# Bias_Current_Source.net
KiCad netlist of a schematic drawn in Altium Designer
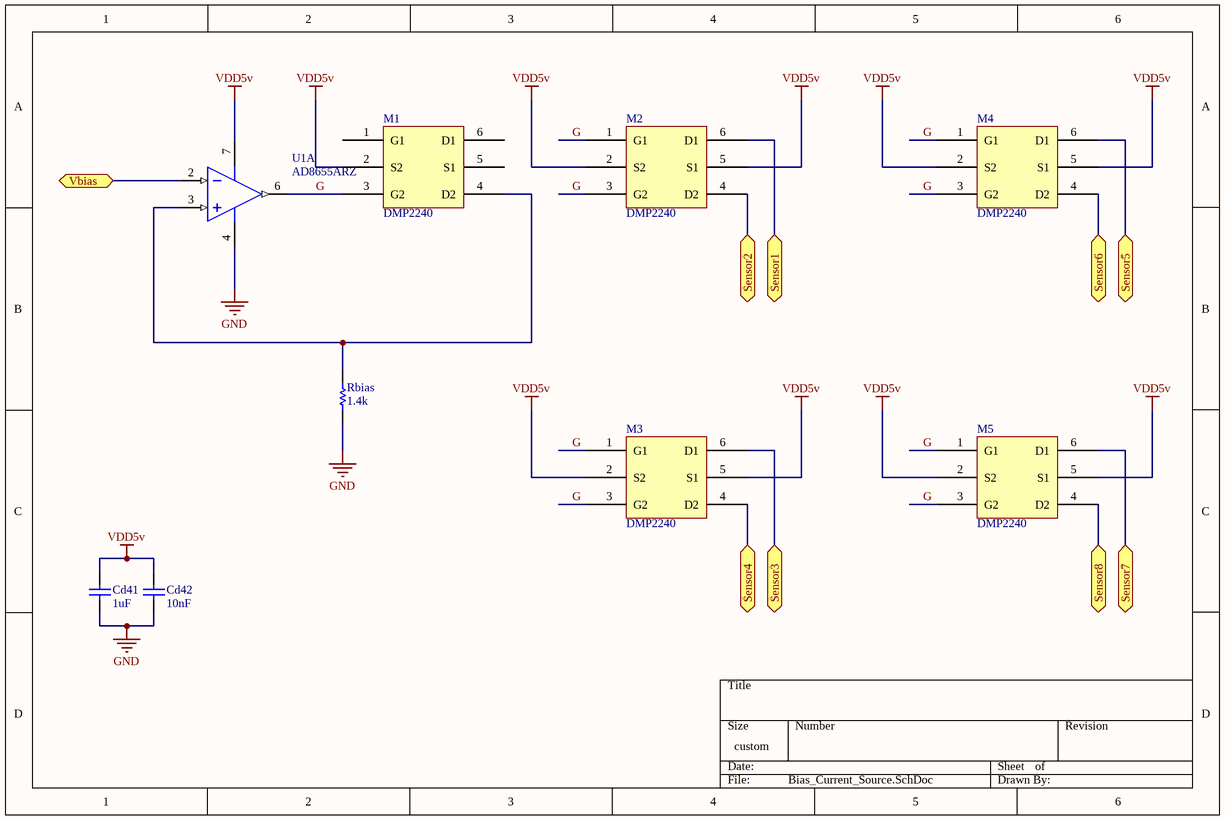
[diagram p0: Bias_Current_Source.SchDoc]

(export (version "E")
  (design (tool "Eeschema 10.0.6"))
  (components
    (comp (ref "Cd41")
      (value "1uF")
      (footprint "1608[0603]")
      (description "Capacitor")
      (fields (field (name "Comment") "Cap") (field (name "PUBLISHER") "Altium Limited"))
      (libsource (lib "Miscellaneous Devices") (part "Cap"))
    )
    (comp (ref "Cd42")
      (value "10nF")
      (footprint "1608[0603]")
      (description "Capacitor")
      (fields (field (name "Comment") "Cap") (field (name "PUBLISHER") "Altium Limited"))
      (libsource (lib "Miscellaneous Devices") (part "Cap"))
    )
    (comp (ref "M1") (value "DMP2240") (footprint "SO-G6/E2.4") (libsource (lib "custom") (part "DMP2240")))
    (comp (ref "M2") (value "DMP2240") (footprint "SO-G6/E2.4") (libsource (lib "custom") (part "DMP2240")))
    (comp (ref "M3") (value "DMP2240") (footprint "SO-G6/E2.4") (libsource (lib "custom") (part "DMP2240")))
    (comp (ref "M4") (value "DMP2240") (footprint "SO-G6/E2.4") (libsource (lib "custom") (part "DMP2240")))
    (comp (ref "M5") (value "DMP2240") (footprint "SO-G6/E2.4") (libsource (lib "custom") (part "DMP2240")))
    (comp (ref "Rbias")
      (value "1.4k")
      (footprint "1608[0603]")
      (description "Resistor")
      (fields (field (name "Comment") "Res1") (field (name "PUBLISHER") "Altium Limited"))
      (libsource (lib "Miscellaneous Devices") (part "Res1"))
    )
    (comp (ref "U1")
      (value "AD8655ARZ")
      (footprint "ADI-R-8_N")
      (fields (field (name "GENERIC PART NUMBER") "AD8655") (field (name "MANUFACTURER") "Analog Devices"))
      (libsource (lib "Analog Devices Operational Amplifiers") (part "AD8655ARZ"))
    )
  )
  (nets
    (net (code "1") (name "/G") (class "Default")
      (node (ref "M1") (pin "3") (pinfunction "G2_3") (pintype "passive"))
      (node (ref "M2") (pin "1") (pinfunction "G1_1") (pintype "passive"))
      (node (ref "M2") (pin "3") (pinfunction "G2_3") (pintype "passive"))
      (node (ref "M3") (pin "1") (pinfunction "G1_1") (pintype "passive"))
      (node (ref "M3") (pin "3") (pinfunction "G2_3") (pintype "passive"))
      (node (ref "M4") (pin "1") (pinfunction "G1_1") (pintype "passive"))
      (node (ref "M4") (pin "3") (pinfunction "G2_3") (pintype "passive"))
      (node (ref "M5") (pin "1") (pinfunction "G1_1") (pintype "passive"))
      (node (ref "M5") (pin "3") (pinfunction "G2_3") (pintype "passive"))
      (node (ref "U1") (pin "6") (pinfunction "OUT_6") (pintype "output"))
    )
    (net (code "2") (name "/Sensor1") (class "Default")
      (node (ref "M2") (pin "6") (pinfunction "D1_6") (pintype "passive"))
    )
    (net (code "3") (name "/Sensor2") (class "Default")
      (node (ref "M2") (pin "4") (pinfunction "D2_4") (pintype "passive"))
    )
    (net (code "4") (name "/Sensor3") (class "Default")
      (node (ref "M3") (pin "6") (pinfunction "D1_6") (pintype "passive"))
    )
    (net (code "5") (name "/Sensor4") (class "Default")
      (node (ref "M3") (pin "4") (pinfunction "D2_4") (pintype "passive"))
    )
    (net (code "6") (name "/Sensor5") (class "Default")
      (node (ref "M4") (pin "6") (pinfunction "D1_6") (pintype "passive"))
    )
    (net (code "7") (name "/Sensor6") (class "Default")
      (node (ref "M4") (pin "4") (pinfunction "D2_4") (pintype "passive"))
    )
    (net (code "8") (name "/Sensor7") (class "Default")
      (node (ref "M5") (pin "6") (pinfunction "D1_6") (pintype "passive"))
    )
    (net (code "9") (name "/Sensor8") (class "Default")
      (node (ref "M5") (pin "4") (pinfunction "D2_4") (pintype "passive"))
    )
    (net (code "10") (name "/Vbias") (class "Default")
      (node (ref "U1") (pin "2") (pinfunction "-IN_2") (pintype "input"))
    )
    (net (code "11") (name "GND") (class "Default")
      (node (ref "Cd41") (pin "2") (pinfunction "2_2") (pintype "passive"))
      (node (ref "Cd42") (pin "2") (pinfunction "2_2") (pintype "passive"))
      (node (ref "Rbias") (pin "2") (pinfunction "2_2") (pintype "passive"))
      (node (ref "U1") (pin "4") (pinfunction "-V_4") (pintype "power_in"))
    )
    (net (code "12") (name "Net-(M1-D2)") (class "Default")
      (node (ref "M1") (pin "4") (pinfunction "D2_4") (pintype "passive"))
      (node (ref "Rbias") (pin "1") (pinfunction "1_1") (pintype "passive"))
      (node (ref "U1") (pin "3") (pinfunction "+IN_3") (pintype "input"))
    )
    (net (code "13") (name "VDD5v") (class "Default")
      (node (ref "Cd41") (pin "1") (pinfunction "1_1") (pintype "passive"))
      (node (ref "Cd42") (pin "1") (pinfunction "1_1") (pintype "passive"))
      (node (ref "M1") (pin "2") (pinfunction "S2_2") (pintype "passive"))
      (node (ref "M2") (pin "2") (pinfunction "S2_2") (pintype "passive"))
      (node (ref "M2") (pin "5") (pinfunction "S1_5") (pintype "passive"))
      (node (ref "M3") (pin "2") (pinfunction "S2_2") (pintype "passive"))
      (node (ref "M3") (pin "5") (pinfunction "S1_5") (pintype "passive"))
      (node (ref "M4") (pin "2") (pinfunction "S2_2") (pintype "passive"))
      (node (ref "M4") (pin "5") (pinfunction "S1_5") (pintype "passive"))
      (node (ref "M5") (pin "2") (pinfunction "S2_2") (pintype "passive"))
      (node (ref "M5") (pin "5") (pinfunction "S1_5") (pintype "passive"))
      (node (ref "U1") (pin "7") (pinfunction "+V_7") (pintype "power_in"))
    )
    (net (code "14") (name "unconnected-(M1-D1-Pad6)") (class "Default")
      (node (ref "M1") (pin "6") (pinfunction "D1_6") (pintype "passive"))
    )
    (net (code "15") (name "unconnected-(M1-G1-Pad1)") (class "Default")
      (node (ref "M1") (pin "1") (pinfunction "G1_1") (pintype "passive"))
    )
    (net (code "16") (name "unconnected-(M1-S1-Pad5)") (class "Default")
      (node (ref "M1") (pin "5") (pinfunction "S1_5") (pintype "passive"))
    )
  )
)
